# Nixie_MCU_PWR.net
KiCad netlist of a schematic drawn in Altium Designer
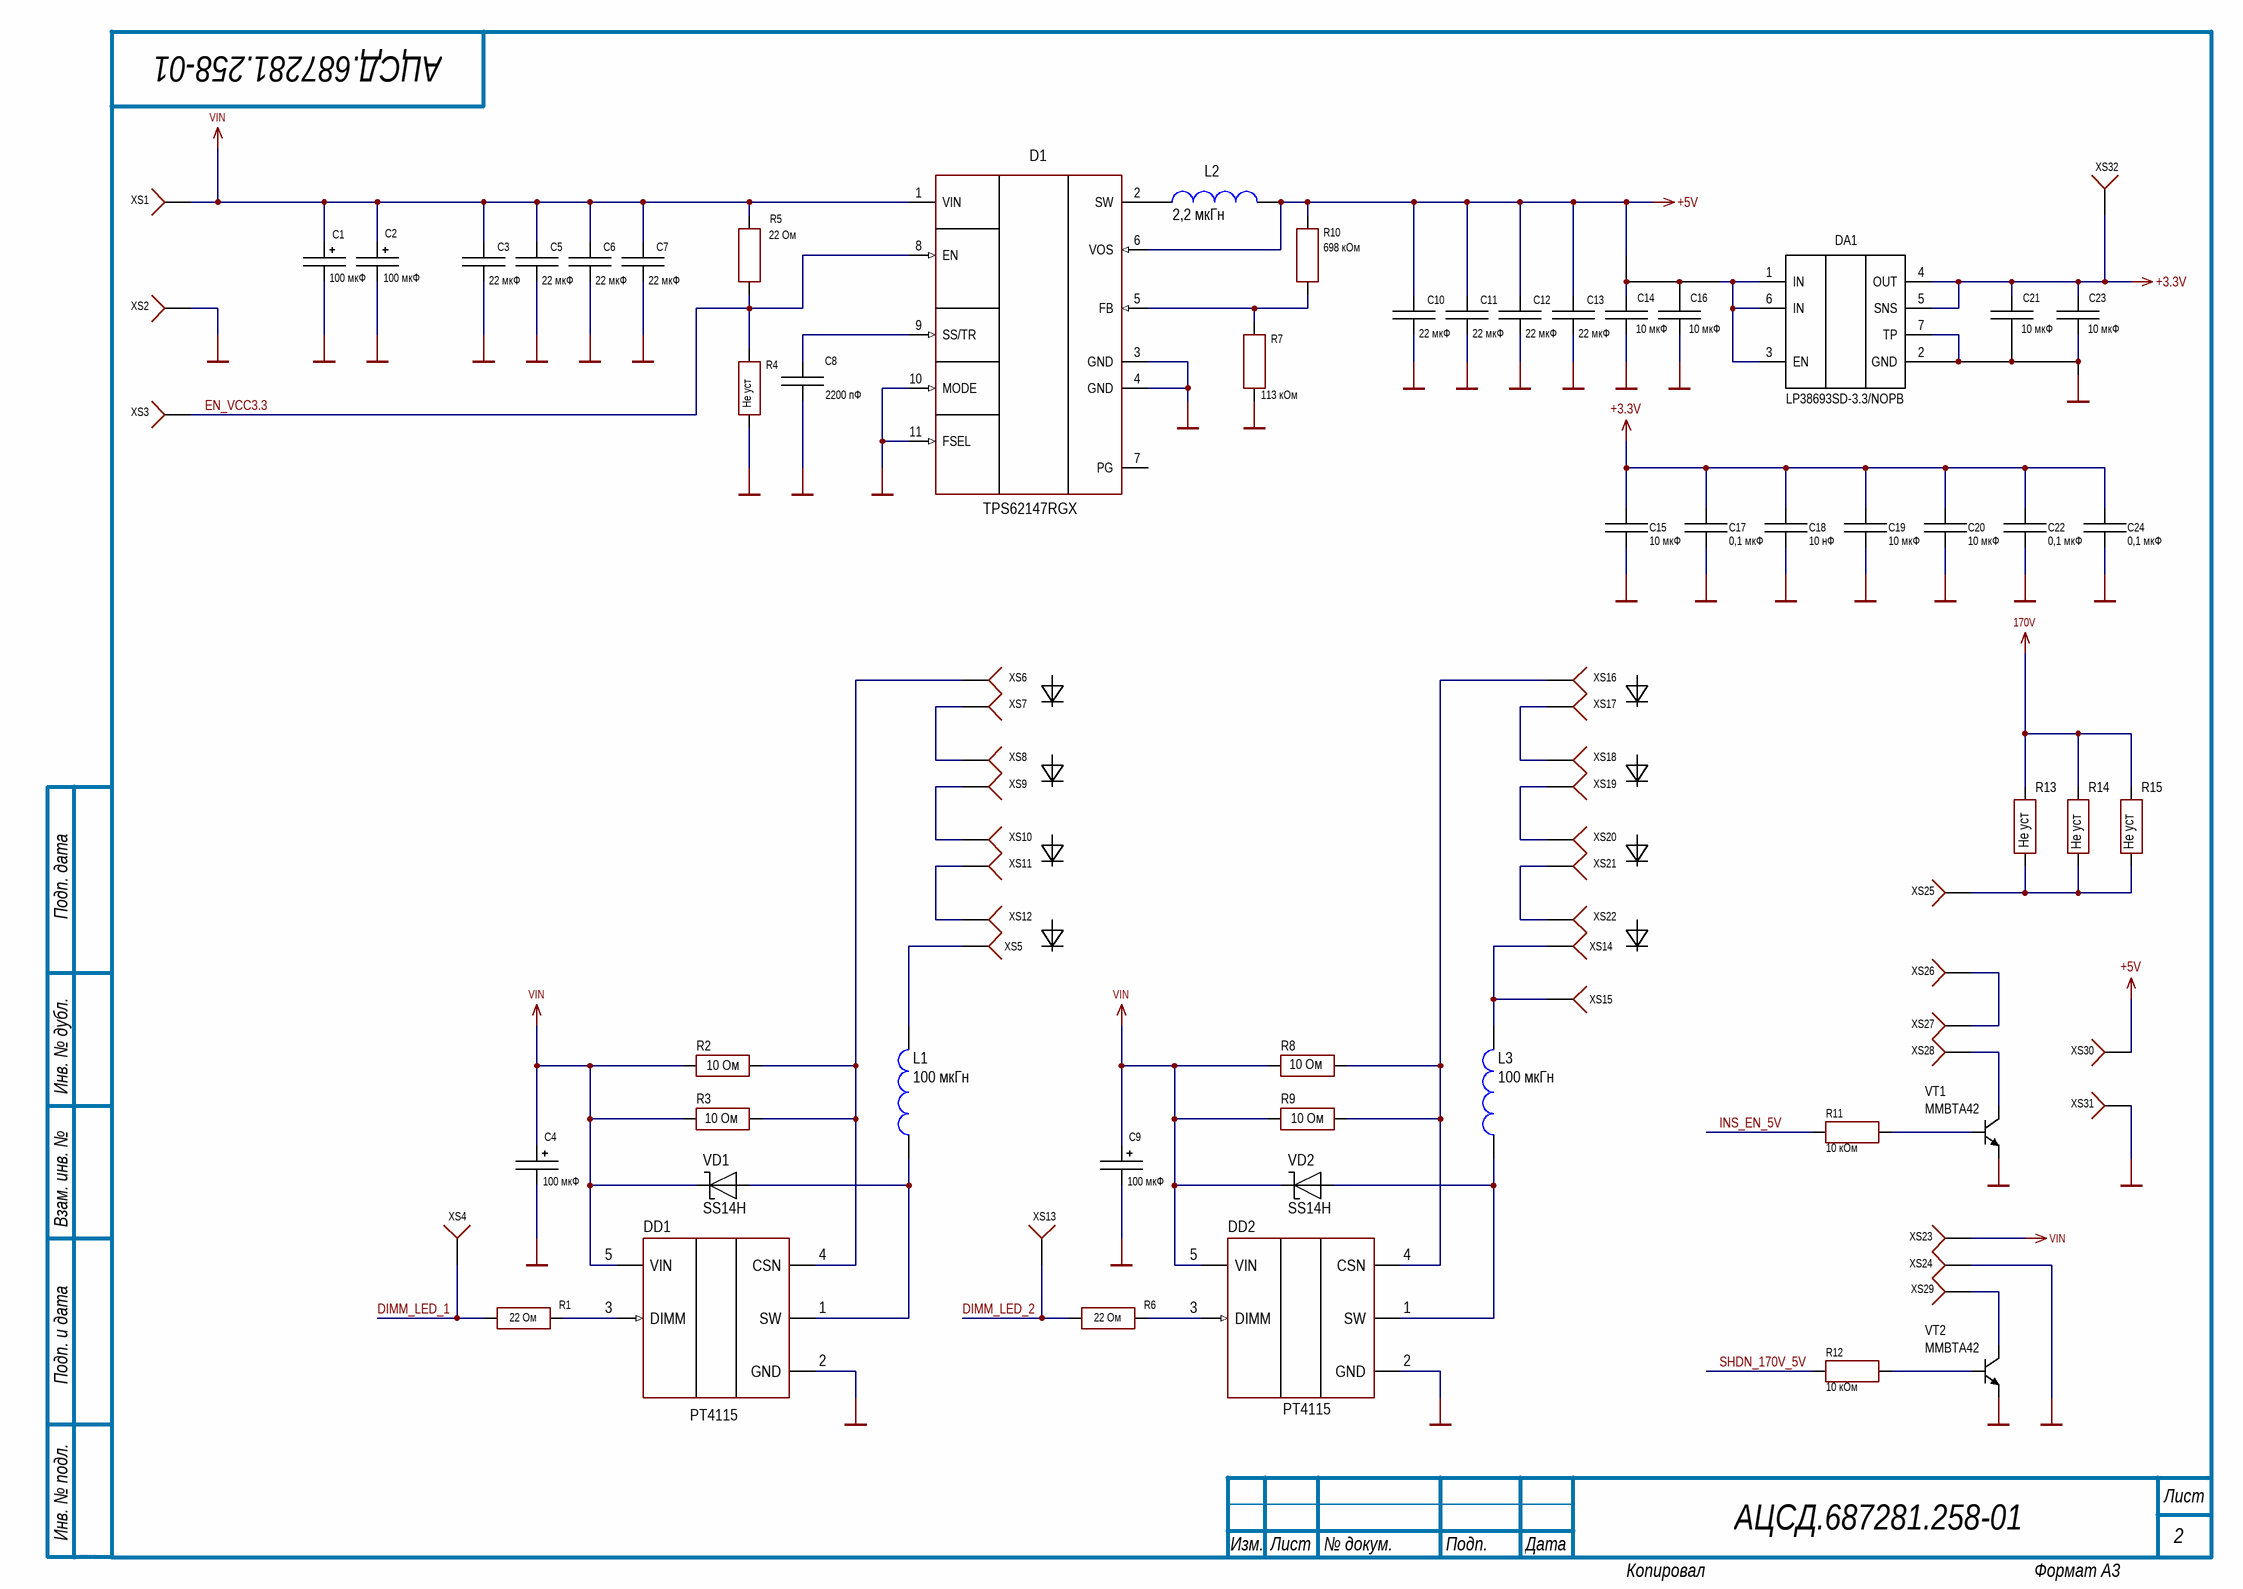
[diagram p0: Nixie_MCU_PWR.SchDoc]

(export (version "E")
  (design (tool "Eeschema 10.0.6"))
  (components
    (comp (ref "C1")
      (value "100 мкФ")
      (footprint "CAP: D5H5.8")
      (fields
        (field (name "MANUFACTURER") "Panasonic")
        (field (name "PARTNUMBER") "EEE-FT1C101AR")
        (field (name "VALUEMANUFACTURERPARTNUMBER") "Aluminium capacitor, 100 мкФ, , ±20%, , 5×5×5.3, -55...+105°C")
      )
      (libsource (lib "Capacitor") (part "Aluminium"))
    )
    (comp (ref "C2")
      (value "100 мкФ")
      (footprint "CAP: D5H5.8")
      (fields
        (field (name "MANUFACTURER") "Panasonic")
        (field (name "PARTNUMBER") "EEE-FT1C101AR")
        (field (name "VALUEMANUFACTURERPARTNUMBER") "Aluminium capacitor, 100 мкФ, , ±20%, , 5×5×5.3, -55...+105°C")
      )
      (libsource (lib "Capacitor") (part "Aluminium"))
    )
    (comp (ref "C3")
      (value "22 мкФ")
      (footprint "CAP: 0805R")
      (fields (field (name "TOLERANCE") "±20%"))
      (libsource (lib "") (part "Ceramic_0603_1"))
    )
    (comp (ref "C4")
      (value "100 мкФ")
      (footprint "CAP: D5H5.8")
      (fields
        (field (name "MANUFACTURER") "Panasonic")
        (field (name "PARTNUMBER") "EEE-FT1C101AR")
        (field (name "VALUEMANUFACTURERPARTNUMBER") "Aluminium capacitor, 100 мкФ, , ±20%, , 5×5×5.3, -55...+105°C")
      )
      (libsource (lib "Capacitor") (part "Aluminium"))
    )
    (comp (ref "C5")
      (value "22 мкФ")
      (footprint "CAP: 0805R")
      (fields (field (name "TOLERANCE") "±20%"))
      (libsource (lib "") (part "Ceramic_0603_1"))
    )
    (comp (ref "C6")
      (value "22 мкФ")
      (footprint "CAP: 0805R")
      (fields (field (name "TOLERANCE") "±20%"))
      (libsource (lib "") (part "Ceramic_0603_1"))
    )
    (comp (ref "C7")
      (value "22 мкФ")
      (footprint "CAP: 0805R")
      (fields (field (name "TOLERANCE") "±20%"))
      (libsource (lib "") (part "Ceramic_0603_1"))
    )
    (comp (ref "C8")
      (value "2200 пФ")
      (footprint "CAP: 0402R")
      (fields
        (field (name "MANUFACTURER") "Murata")
        (field (name "VALUEMANUFACTURERPARTNUMBER") "Ceramic capacitor, 2200 пФ, X7R, ± 10 %, , 0402, -55...+125°C")
        (field (name "TOLERANCE") "± 10 %")
      )
      (libsource (lib "Capacitor") (part "Ceramic_0402"))
    )
    (comp (ref "C9")
      (value "100 мкФ")
      (footprint "CAP: D5H5.8")
      (fields
        (field (name "MANUFACTURER") "Panasonic")
        (field (name "PARTNUMBER") "EEE-FT1C101AR")
        (field (name "VALUEMANUFACTURERPARTNUMBER") "Aluminium capacitor, 100 мкФ, , ±20%, , 5×5×5.3, -55...+105°C")
      )
      (libsource (lib "Capacitor") (part "Aluminium"))
    )
    (comp (ref "C10")
      (value "22 мкФ")
      (footprint "CAP: 0805R")
      (fields (field (name "TOLERANCE") "±20%"))
      (libsource (lib "") (part "Ceramic_0603_1"))
    )
    (comp (ref "C11")
      (value "22 мкФ")
      (footprint "CAP: 0805R")
      (fields (field (name "TOLERANCE") "±20%"))
      (libsource (lib "") (part "Ceramic_0603_1"))
    )
    (comp (ref "C12")
      (value "22 мкФ")
      (footprint "CAP: 0805R")
      (fields (field (name "TOLERANCE") "±20%"))
      (libsource (lib "") (part "Ceramic_0603_1"))
    )
    (comp (ref "C13")
      (value "22 мкФ")
      (footprint "CAP: 0805R")
      (fields (field (name "TOLERANCE") "±20%"))
      (libsource (lib "") (part "Ceramic_0603_1"))
    )
    (comp (ref "C14")
      (value "10 мкФ")
      (footprint "CAP: 0603R")
      (fields
        (field (name "MANUFACTURER") "Yageo")
        (field (name "VALUEMANUFACTURERPARTNUMBER") "Ceramic capacitor, 10 мкФ, X7R, ±10%, 16V, 0603, -55...+125°C")
        (field (name "TOLERANCE") "±10%")
      )
      (libsource (lib "Capacitor") (part "Ceramic_0603"))
    )
    (comp (ref "C15")
      (value "10 мкФ")
      (footprint "CAP: 0603R")
      (fields
        (field (name "MANUFACTURER") "Yageo")
        (field (name "VALUEMANUFACTURERPARTNUMBER") "Ceramic capacitor, 10 мкФ, X7R, ±10%, 16V, 0603, -55...+125°C")
        (field (name "TOLERANCE") "±10%")
      )
      (libsource (lib "Capacitor") (part "Ceramic_0603"))
    )
    (comp (ref "C16")
      (value "10 мкФ")
      (footprint "CAP: 0603R")
      (fields
        (field (name "MANUFACTURER") "Yageo")
        (field (name "VALUEMANUFACTURERPARTNUMBER") "Ceramic capacitor, 10 мкФ, X7R, ±10%, 16V, 0603, -55...+125°C")
        (field (name "TOLERANCE") "±10%")
      )
      (libsource (lib "Capacitor") (part "Ceramic_0603"))
    )
    (comp (ref "C17")
      (value "0,1 мкФ")
      (footprint "CAP: 0402R")
      (fields
        (field (name "MANUFACTURER") "Murata")
        (field (name "PARTNUMBER") "GCM155R71H104KE02#")
        (field (name "VALUEMANUFACTURERPARTNUMBER") "Ceramic capacitor, 0,1 мкФ, X7R, ± 10 %, , 0402, -55...+125°C")
      )
      (libsource (lib "Capacitor") (part "Ceramic_0402"))
    )
    (comp (ref "C18")
      (value "10 нФ")
      (footprint "CAP: 0402R")
      (fields
        (field (name "MANUFACTURER") "Murata")
        (field (name "PARTNUMBER") "GCM155R71H104KE02#")
        (field (name "VALUEMANUFACTURERPARTNUMBER") "Ceramic capacitor, 10 нФ, X7R, ± 10 %, , 0402, -55...+125°C")
      )
      (libsource (lib "Capacitor") (part "Ceramic_0402"))
    )
    (comp (ref "C19")
      (value "10 мкФ")
      (footprint "CAP: 0603R")
      (fields
        (field (name "MANUFACTURER") "Yageo")
        (field (name "VALUEMANUFACTURERPARTNUMBER") "Ceramic capacitor, 10 мкФ, X7R, ±10%, 16V, 0603, -55...+125°C")
        (field (name "TOLERANCE") "±10%")
      )
      (libsource (lib "Capacitor") (part "Ceramic_0603"))
    )
    (comp (ref "C20")
      (value "10 мкФ")
      (footprint "CAP: 0603R")
      (fields
        (field (name "MANUFACTURER") "Yageo")
        (field (name "VALUEMANUFACTURERPARTNUMBER") "Ceramic capacitor, 10 мкФ, X7R, ±10%, 16V, 0603, -55...+125°C")
        (field (name "TOLERANCE") "±10%")
      )
      (libsource (lib "Capacitor") (part "Ceramic_0603"))
    )
    (comp (ref "C21")
      (value "10 мкФ")
      (footprint "CAP: 0603R")
      (fields
        (field (name "MANUFACTURER") "Yageo")
        (field (name "VALUEMANUFACTURERPARTNUMBER") "Ceramic capacitor, 10 мкФ, X7R, ±10%, 16V, 0603, -55...+125°C")
        (field (name "TOLERANCE") "±10%")
      )
      (libsource (lib "Capacitor") (part "Ceramic_0603"))
    )
    (comp (ref "C22")
      (value "0,1 мкФ")
      (footprint "CAP: 0402R")
      (fields
        (field (name "MANUFACTURER") "Murata")
        (field (name "PARTNUMBER") "GCM155R71H104KE02#")
        (field (name "VALUEMANUFACTURERPARTNUMBER") "Ceramic capacitor, 0,1 мкФ, X7R, ± 10 %, , 0402, -55...+125°C")
      )
      (libsource (lib "Capacitor") (part "Ceramic_0402"))
    )
    (comp (ref "C23")
      (value "10 мкФ")
      (footprint "CAP: 0603R")
      (fields
        (field (name "MANUFACTURER") "Yageo")
        (field (name "VALUEMANUFACTURERPARTNUMBER") "Ceramic capacitor, 10 мкФ, X7R, ±10%, 16V, 0603, -55...+125°C")
        (field (name "TOLERANCE") "±10%")
      )
      (libsource (lib "Capacitor") (part "Ceramic_0603"))
    )
    (comp (ref "C24")
      (value "0,1 мкФ")
      (footprint "CAP: 0402R")
      (fields
        (field (name "MANUFACTURER") "Murata")
        (field (name "PARTNUMBER") "GCM155R71H104KE02#")
        (field (name "VALUEMANUFACTURERPARTNUMBER") "Ceramic capacitor, 0,1 мкФ, X7R, ± 10 %, , 0402, -55...+125°C")
      )
      (libsource (lib "Capacitor") (part "Ceramic_0402"))
    )
    (comp (ref "D1")
      (value "~")
      (footprint "11-VQFN(RGX)")
      (description "3-V to 17-V 2-A Step-Down Converters")
      (fields (field (name "MANUFACTURER") "Texas Instruments") (field (name "PARTNUMBER") "TPS62147RGX"))
      (libsource (lib "IC. Power supply") (part "TPS62147RGX"))
    )
    (comp (ref "DA1")
      (value "LP38693SD-3.3/NOPB")
      (footprint "StandardCase:6-WSON")
      (description "LINEAR 3.3V 500MA 6WSON")
      (fields
        (field (name "MANUFACTURER") "Texas Instruments")
        (field (name "VALUEMANUFACTURERPARTNUMBER") "LDO, (2.7 V to 10 V), , output 3.3V, 500 mA, -40…+125, WSON (6)")
      )
      (libsource (lib "IC. Power supply") (part "LP38693SD-3.3/NOPB"))
    )
    (comp (ref "DD1")
      (value "~")
      (footprint "5-SOT-89")
      (description "LED current driver")
      (fields
        (field (name "VALUEMANUFACTURERPARTNUMBER") "LED current driver, 6 V to 30 v, , , 1.2A, -40…+125, SOT89-5")
        (field (name "PARTNUMBER") "PT4115")
      )
      (libsource (lib "IC. Power supply") (part "PT4115"))
    )
    (comp (ref "DD2")
      (value "~")
      (footprint "5-SOT-89")
      (description "LED current driver")
      (fields
        (field (name "VALUEMANUFACTURERPARTNUMBER") "LED current driver, 6 V to 30 v, , , 1.2A, -40…+125, SOT89-5")
        (field (name "PARTNUMBER") "PT4115")
      )
      (libsource (lib "IC. Power supply") (part "PT4115"))
    )
    (comp (ref "L1")
      (value "100 мкГн")
      (footprint "IND: VLS5045EX")
      (description "Power Inductor, 5.0x5.0x4.5mm, -40°C to +105°C")
      (fields
        (field (name "PARTNUMBER") "VLS5045EX-101M")
        (field (name "VALUEMANUFACTURERPARTNUMBER") "Fixed inductor, 100 мкГн, , , , -40...+125°C")
      )
      (libsource (lib "Inductor") (part "VLS5045EX"))
    )
    (comp (ref "L2")
      (value "2,2 мкГн")
      (footprint "IND: VLS5045EX")
      (description "Power Inductor, 5.0x5.0x4.5mm, -40°C to +105°C")
      (fields
        (field (name "PARTNUMBER") "VLS5045EX-2R2N")
        (field (name "VALUEMANUFACTURERPARTNUMBER") "Fixed inductor, 2,2 мкГн, , , , -40...+125°C")
      )
      (libsource (lib "Inductor") (part "VLS5045EX"))
    )
    (comp (ref "L3")
      (value "100 мкГн")
      (footprint "IND: VLS5045EX")
      (description "Power Inductor, 5.0x5.0x4.5mm, -40°C to +105°C")
      (fields
        (field (name "PARTNUMBER") "VLS5045EX-101M")
        (field (name "VALUEMANUFACTURERPARTNUMBER") "Fixed inductor, 100 мкГн, , , , -40...+125°C")
      )
      (libsource (lib "Inductor") (part "VLS5045EX"))
    )
    (comp (ref "R1")
      (value "22 Ом")
      (footprint "RES: 0402_ASK")
      (fields (field (name "POWER") "0.063 Вт") (field (name "TOLERANCE") "±1%"))
      (libsource (lib "") (part "Resistor_0402_2"))
    )
    (comp (ref "R2")
      (value "10 Ом")
      (footprint "RES: 0603_ASK")
      (fields
        (field (name "MANUFACTURER") "Yageo")
        (field (name "PARTNUMBER") "RC0603JR-07100RL")
        (field (name "VALUEMANUFACTURERPARTNUMBER") "Resistor film, 10 Ом, ±1%, 0603, 0.1W, -55...+125°C")
      )
      (libsource (lib "Resistor") (part "Resistor_0603"))
    )
    (comp (ref "R3")
      (value "10 Ом")
      (footprint "RES: 0603_ASK")
      (fields
        (field (name "MANUFACTURER") "Yageo")
        (field (name "PARTNUMBER") "RC0603JR-07100RL")
        (field (name "VALUEMANUFACTURERPARTNUMBER") "Resistor film, 10 Ом, ±1%, 0603, 0.1W, -55...+125°C")
      )
      (libsource (lib "Resistor") (part "Resistor_0603"))
    )
    (comp (ref "R4")
      (value "Не уст")
      (footprint "RES: 0402_ASK")
      (fields (field (name "POWER") "0.063 Вт") (field (name "TOLERANCE") "±1%"))
      (libsource (lib "Resistor") (part "Resistor_0402"))
    )
    (comp (ref "R5")
      (value "22 Ом")
      (footprint "RES: 0402_ASK")
      (fields (field (name "POWER") "0.063 Вт") (field (name "TOLERANCE") "±1%"))
      (libsource (lib "Resistor") (part "Resistor_0402"))
    )
    (comp (ref "R6")
      (value "22 Ом")
      (footprint "RES: 0402_ASK")
      (fields (field (name "POWER") "0.063 Вт") (field (name "TOLERANCE") "±1%"))
      (libsource (lib "") (part "Resistor_0402_2"))
    )
    (comp (ref "R7")
      (value "113 кОм")
      (footprint "RES: 0402_ASK")
      (fields (field (name "POWER") "0.063 Вт") (field (name "TOLERANCE") "±1%"))
      (libsource (lib "Resistor") (part "Resistor_0402"))
    )
    (comp (ref "R8")
      (value "10 Ом")
      (footprint "RES: 0603_ASK")
      (fields
        (field (name "MANUFACTURER") "Yageo")
        (field (name "PARTNUMBER") "RC0603JR-07100RL")
        (field (name "VALUEMANUFACTURERPARTNUMBER") "Resistor film, 10 Ом, ±1%, 0603, 0.1W, -55...+125°C")
      )
      (libsource (lib "Resistor") (part "Resistor_0603"))
    )
    (comp (ref "R9")
      (value "10 Ом")
      (footprint "RES: 0603_ASK")
      (fields
        (field (name "MANUFACTURER") "Yageo")
        (field (name "PARTNUMBER") "RC0603JR-07100RL")
        (field (name "VALUEMANUFACTURERPARTNUMBER") "Resistor film, 10 Ом, ±1%, 0603, 0.1W, -55...+125°C")
      )
      (libsource (lib "Resistor") (part "Resistor_0603"))
    )
    (comp (ref "R10")
      (value "698 кОм")
      (footprint "RES: 0402_ASK")
      (fields (field (name "POWER") "0.063 Вт") (field (name "TOLERANCE") "±1%"))
      (libsource (lib "Resistor") (part "Resistor_0402"))
    )
    (comp (ref "R11")
      (value "10 кОм")
      (footprint "RES: 0402_ASK")
      (fields (field (name "POWER") "0.063 Вт") (field (name "TOLERANCE") "±1%"))
      (libsource (lib "") (part "Resistor_0402_1"))
    )
    (comp (ref "R12")
      (value "10 кОм")
      (footprint "RES: 0402_ASK")
      (fields (field (name "POWER") "0.063 Вт") (field (name "TOLERANCE") "±1%"))
      (libsource (lib "") (part "Resistor_0402_1"))
    )
    (comp (ref "R13")
      (value "Не уст")
      (footprint "RES: 0603_ASK")
      (fields
        (field (name "MANUFACTURER") "Yageo")
        (field (name "PARTNUMBER") "RC0603JR-07100RL")
        (field (name "VALUEMANUFACTURERPARTNUMBER") "Resistor film, Не уст, ±1%, 0603, 0.1W, -55...+125°C")
      )
      (libsource (lib "") (part "Resistor_0603_1"))
    )
    (comp (ref "R14")
      (value "Не уст")
      (footprint "RES: 0603_ASK")
      (fields
        (field (name "MANUFACTURER") "Yageo")
        (field (name "PARTNUMBER") "RC0603JR-07100RL")
        (field (name "VALUEMANUFACTURERPARTNUMBER") "Resistor film, Не уст, ±1%, 0603, 0.1W, -55...+125°C")
      )
      (libsource (lib "") (part "Resistor_0603_1"))
    )
    (comp (ref "R15")
      (value "Не уст")
      (footprint "RES: 0603_ASK")
      (fields
        (field (name "MANUFACTURER") "Yageo")
        (field (name "PARTNUMBER") "RC0603JR-07100RL")
        (field (name "VALUEMANUFACTURERPARTNUMBER") "Resistor film, Не уст, ±1%, 0603, 0.1W, -55...+125°C")
      )
      (libsource (lib "") (part "Resistor_0603_1"))
    )
    (comp (ref "VD1")
      (value "~")
      (footprint "StandardCase:DIODE: SMA")
      (fields
        (field (name "MANUFACTURER") "Diodes Incorporated")
        (field (name "VALUEMANUFACTURERPARTNUMBER") "Schottky diode, 80V, 500mA, 1V, 15pF, SOD-123, -55...+150°C")
        (field (name "VOLTAGE") "80V")
        (field (name "PARTNUMBER") "SS14H")
      )
      (libsource (lib "Diode") (part "Schottky_single"))
    )
    (comp (ref "VD2")
      (value "~")
      (footprint "StandardCase:DIODE: SMA")
      (fields
        (field (name "MANUFACTURER") "Diodes Incorporated")
        (field (name "VALUEMANUFACTURERPARTNUMBER") "Schottky diode, 80V, 500mA, 1V, 15pF, SOD-123, -55...+150°C")
        (field (name "VOLTAGE") "80V")
        (field (name "PARTNUMBER") "SS14H")
      )
      (libsource (lib "Diode") (part "Schottky_single"))
    )
    (comp (ref "VT1")
      (value "~")
      (footprint "StandardCase:SOT23")
      (fields
        (field (name "MANUFACTURER") "ON Semiconductor")
        (field (name "VALUEMANUFACTURERPARTNUMBER") "NPN transistor, 45V, 100mA, 100MHz, 300mW, 0.6V, 420, SOT-23, -55...+125°C")
        (field (name "PARTNUMBER") "MMBTA42")
      )
      (libsource (lib "Transistor") (part "BJT_NPN_132"))
    )
    (comp (ref "VT2")
      (value "~")
      (footprint "StandardCase:SOT23")
      (fields
        (field (name "MANUFACTURER") "ON Semiconductor")
        (field (name "VALUEMANUFACTURERPARTNUMBER") "NPN transistor, 45V, 100mA, 100MHz, 300mW, 0.6V, 420, SOT-23, -55...+125°C")
        (field (name "PARTNUMBER") "MMBTA42")
      )
      (libsource (lib "Transistor") (part "BJT_NPN_132"))
    )
    (comp (ref "XS1") (value "~") (footprint "CON: PLD-1") (libsource (lib "Connector") (part "Контр.точка")))
    (comp (ref "XS2") (value "~") (footprint "CON: PLD-1") (libsource (lib "Connector") (part "Контр.точка")))
    (comp (ref "XS3") (value "~") (footprint "CON: PLD-1") (libsource (lib "Connector") (part "Контр.точка")))
    (comp (ref "XS4") (value "~") (footprint "CON: PLD-1") (libsource (lib "Connector") (part "Контр.точка")))
    (comp (ref "XS5") (value "~") (footprint "CON: PLD-1") (libsource (lib "Connector") (part "Контр.точка")))
    (comp (ref "XS6") (value "~") (footprint "CON: PLD-1") (libsource (lib "Connector") (part "Контр.точка")))
    (comp (ref "XS7") (value "~") (footprint "CON: PLD-1") (libsource (lib "Connector") (part "Контр.точка")))
    (comp (ref "XS8") (value "~") (footprint "CON: PLD-1") (libsource (lib "Connector") (part "Контр.точка")))
    (comp (ref "XS9") (value "~") (footprint "CON: PLD-1") (libsource (lib "Connector") (part "Контр.точка")))
    (comp (ref "XS10")
      (value "~")
      (footprint "CON: PLD-1")
      (libsource (lib "Connector") (part "Контр.точка"))
    )
    (comp (ref "XS11")
      (value "~")
      (footprint "CON: PLD-1")
      (libsource (lib "Connector") (part "Контр.точка"))
    )
    (comp (ref "XS12")
      (value "~")
      (footprint "CON: PLD-1")
      (libsource (lib "Connector") (part "Контр.точка"))
    )
    (comp (ref "XS13")
      (value "~")
      (footprint "CON: PLD-1")
      (libsource (lib "Connector") (part "Контр.точка"))
    )
    (comp (ref "XS14")
      (value "~")
      (footprint "CON: PLD-1")
      (libsource (lib "Connector") (part "Контр.точка"))
    )
    (comp (ref "XS15")
      (value "~")
      (footprint "CON: PLD-1")
      (libsource (lib "Connector") (part "Контр.точка"))
    )
    (comp (ref "XS16")
      (value "~")
      (footprint "CON: PLD-1")
      (libsource (lib "Connector") (part "Контр.точка"))
    )
    (comp (ref "XS17")
      (value "~")
      (footprint "CON: PLD-1")
      (libsource (lib "Connector") (part "Контр.точка"))
    )
    (comp (ref "XS18")
      (value "~")
      (footprint "CON: PLD-1")
      (libsource (lib "Connector") (part "Контр.точка"))
    )
    (comp (ref "XS19")
      (value "~")
      (footprint "CON: PLD-1")
      (libsource (lib "Connector") (part "Контр.точка"))
    )
    (comp (ref "XS20")
      (value "~")
      (footprint "CON: PLD-1")
      (libsource (lib "Connector") (part "Контр.точка"))
    )
    (comp (ref "XS21")
      (value "~")
      (footprint "CON: PLD-1")
      (libsource (lib "Connector") (part "Контр.точка"))
    )
    (comp (ref "XS22")
      (value "~")
      (footprint "CON: PLD-1")
      (libsource (lib "Connector") (part "Контр.точка"))
    )
    (comp (ref "XS23")
      (value "~")
      (footprint "CON: PLD-1")
      (libsource (lib "Connector") (part "Контр.точка"))
    )
    (comp (ref "XS24")
      (value "~")
      (footprint "CON: PLD-1")
      (libsource (lib "Connector") (part "Контр.точка"))
    )
    (comp (ref "XS25")
      (value "~")
      (footprint "CON: PLD-1")
      (libsource (lib "Connector") (part "Контр.точка"))
    )
    (comp (ref "XS26")
      (value "~")
      (footprint "CON: PLD-1")
      (libsource (lib "Connector") (part "Контр.точка"))
    )
    (comp (ref "XS27")
      (value "~")
      (footprint "CON: PLD-1")
      (libsource (lib "Connector") (part "Контр.точка"))
    )
    (comp (ref "XS28")
      (value "~")
      (footprint "CON: PLD-1")
      (libsource (lib "Connector") (part "Контр.точка"))
    )
    (comp (ref "XS29")
      (value "~")
      (footprint "CON: PLD-1")
      (libsource (lib "Connector") (part "Контр.точка"))
    )
    (comp (ref "XS30")
      (value "~")
      (footprint "CON: PLD-1")
      (libsource (lib "Connector") (part "Контр.точка"))
    )
    (comp (ref "XS31")
      (value "~")
      (footprint "CON: PLD-1")
      (libsource (lib "Connector") (part "Контр.точка"))
    )
    (comp (ref "XS32")
      (value "~")
      (footprint "CON: PLD-1")
      (libsource (lib "Connector") (part "Контр.точка"))
    )
  )
  (nets
    (net (code "1") (name "+3.3V") (class "Default")
      (node (ref "C15") (pin "2") (pinfunction "2_2") (pintype "power_in"))
      (node (ref "C17") (pin "2") (pinfunction "2_2") (pintype "passive"))
      (node (ref "C18") (pin "2") (pinfunction "2_2") (pintype "passive"))
      (node (ref "C19") (pin "2") (pinfunction "2_2") (pintype "power_in"))
      (node (ref "C20") (pin "2") (pinfunction "2_2") (pintype "power_in"))
      (node (ref "C21") (pin "2") (pinfunction "2_2") (pintype "power_in"))
      (node (ref "C22") (pin "2") (pinfunction "2_2") (pintype "passive"))
      (node (ref "C23") (pin "2") (pinfunction "2_2") (pintype "power_in"))
      (node (ref "C24") (pin "2") (pinfunction "2_2") (pintype "passive"))
      (node (ref "DA1") (pin "4") (pinfunction "OUT_4") (pintype "passive"))
      (node (ref "DA1") (pin "5") (pinfunction "SNS_5") (pintype "passive"))
      (node (ref "XS32") (pin "1") (pinfunction "1_1") (pintype "passive"))
    )
    (net (code "2") (name "+5V") (class "Default")
      (node (ref "C10") (pin "2") (pinfunction "2_2") (pintype "passive"))
      (node (ref "C11") (pin "2") (pinfunction "2_2") (pintype "passive"))
      (node (ref "C12") (pin "2") (pinfunction "2_2") (pintype "passive"))
      (node (ref "C13") (pin "2") (pinfunction "2_2") (pintype "passive"))
      (node (ref "C14") (pin "2") (pinfunction "2_2") (pintype "power_in"))
      (node (ref "C16") (pin "2") (pinfunction "2_2") (pintype "power_in"))
      (node (ref "D1") (pin "6") (pinfunction "VOS_6") (pintype "input"))
      (node (ref "DA1") (pin "1") (pinfunction "IN_1") (pintype "passive"))
      (node (ref "DA1") (pin "3") (pinfunction "EN_3") (pintype "passive"))
      (node (ref "DA1") (pin "6") (pinfunction "IN_6") (pintype "passive"))
      (node (ref "L2") (pin "2") (pinfunction "2_2") (pintype "passive"))
      (node (ref "R10") (pin "1") (pinfunction "1_1") (pintype "passive"))
      (node (ref "XS30") (pin "1") (pinfunction "1_1") (pintype "passive"))
    )
    (net (code "3") (name "/DIMM_LED_1") (class "Default")
      (node (ref "R1") (pin "1") (pinfunction "1_1") (pintype "passive"))
      (node (ref "XS4") (pin "1") (pinfunction "1_1") (pintype "passive"))
    )
    (net (code "4") (name "/DIMM_LED_2") (class "Default")
      (node (ref "R6") (pin "1") (pinfunction "1_1") (pintype "passive"))
      (node (ref "XS13") (pin "1") (pinfunction "1_1") (pintype "passive"))
    )
    (net (code "5") (name "/EN_VCC3.3") (class "Default")
      (node (ref "D1") (pin "8") (pinfunction "EN_8") (pintype "input"))
      (node (ref "R4") (pin "1") (pinfunction "1_1") (pintype "passive"))
      (node (ref "R5") (pin "2") (pinfunction "2_2") (pintype "passive"))
      (node (ref "XS3") (pin "1") (pinfunction "1_1") (pintype "passive"))
    )
    (net (code "6") (name "/INS_EN_5V") (class "Default")
      (node (ref "R11") (pin "2") (pinfunction "2_2") (pintype "passive"))
    )
    (net (code "7") (name "/SHDN_170V_5V") (class "Default")
      (node (ref "R12") (pin "2") (pinfunction "2_2") (pintype "passive"))
    )
    (net (code "8") (name "170V") (class "Default")
      (node (ref "R13") (pin "2") (pinfunction "2_2") (pintype "passive"))
      (node (ref "R14") (pin "2") (pinfunction "2_2") (pintype "passive"))
      (node (ref "R15") (pin "2") (pinfunction "2_2") (pintype "passive"))
    )
    (net (code "9") (name "GND") (class "Default")
      (node (ref "C1") (pin "2") (pinfunction "2_2") (pintype "power_in"))
      (node (ref "C10") (pin "1") (pinfunction "1_1") (pintype "power_in"))
      (node (ref "C11") (pin "1") (pinfunction "1_1") (pintype "power_in"))
      (node (ref "C12") (pin "1") (pinfunction "1_1") (pintype "power_in"))
      (node (ref "C13") (pin "1") (pinfunction "1_1") (pintype "power_in"))
      (node (ref "C14") (pin "1") (pinfunction "1_1") (pintype "power_in"))
      (node (ref "C15") (pin "1") (pinfunction "1_1") (pintype "power_in"))
      (node (ref "C16") (pin "1") (pinfunction "1_1") (pintype "power_in"))
      (node (ref "C17") (pin "1") (pinfunction "1_1") (pintype "power_in"))
      (node (ref "C18") (pin "1") (pinfunction "1_1") (pintype "power_in"))
      (node (ref "C19") (pin "1") (pinfunction "1_1") (pintype "power_in"))
      (node (ref "C2") (pin "2") (pinfunction "2_2") (pintype "power_in"))
      (node (ref "C20") (pin "1") (pinfunction "1_1") (pintype "power_in"))
      (node (ref "C21") (pin "1") (pinfunction "1_1") (pintype "power_in"))
      (node (ref "C22") (pin "1") (pinfunction "1_1") (pintype "power_in"))
      (node (ref "C23") (pin "1") (pinfunction "1_1") (pintype "power_in"))
      (node (ref "C24") (pin "1") (pinfunction "1_1") (pintype "power_in"))
      (node (ref "C3") (pin "1") (pinfunction "1_1") (pintype "power_in"))
      (node (ref "C4") (pin "2") (pinfunction "2_2") (pintype "power_in"))
      (node (ref "C5") (pin "1") (pinfunction "1_1") (pintype "power_in"))
      (node (ref "C6") (pin "1") (pinfunction "1_1") (pintype "power_in"))
      (node (ref "C7") (pin "1") (pinfunction "1_1") (pintype "power_in"))
      (node (ref "C8") (pin "1") (pinfunction "1_1") (pintype "power_in"))
      (node (ref "C9") (pin "2") (pinfunction "2_2") (pintype "power_in"))
      (node (ref "D1") (pin "10") (pinfunction "MODE_10") (pintype "input"))
      (node (ref "D1") (pin "11") (pinfunction "FSEL_11") (pintype "input"))
      (node (ref "D1") (pin "3") (pinfunction "GND_3") (pintype "passive"))
      (node (ref "D1") (pin "4") (pinfunction "GND_4") (pintype "passive"))
      (node (ref "DA1") (pin "2") (pinfunction "GND_2") (pintype "power_in"))
      (node (ref "DA1") (pin "7") (pinfunction "TP_7") (pintype "passive"))
      (node (ref "DD1") (pin "2") (pinfunction "GND_2") (pintype "passive"))
      (node (ref "DD2") (pin "2") (pinfunction "GND_2") (pintype "passive"))
      (node (ref "R4") (pin "2") (pinfunction "2_2") (pintype "passive"))
      (node (ref "R7") (pin "2") (pinfunction "2_2") (pintype "passive"))
      (node (ref "VT1") (pin "2") (pinfunction "E_2") (pintype "passive"))
      (node (ref "VT2") (pin "2") (pinfunction "E_2") (pintype "passive"))
      (node (ref "XS2") (pin "1") (pinfunction "1_1") (pintype "passive"))
      (node (ref "XS24") (pin "1") (pinfunction "1_1") (pintype "passive"))
      (node (ref "XS31") (pin "1") (pinfunction "1_1") (pintype "passive"))
    )
    (net (code "10") (name "Net-(D1-FB)") (class "Default")
      (node (ref "D1") (pin "5") (pinfunction "FB_5") (pintype "input"))
      (node (ref "R10") (pin "2") (pinfunction "2_2") (pintype "passive"))
      (node (ref "R7") (pin "1") (pinfunction "1_1") (pintype "passive"))
    )
    (net (code "11") (name "Net-(D1-SS{slash}TR)") (class "Default")
      (node (ref "C8") (pin "2") (pinfunction "2_2") (pintype "passive"))
      (node (ref "D1") (pin "9") (pinfunction "SS/TR_9") (pintype "input"))
    )
    (net (code "12") (name "Net-(D1-SW)") (class "Default")
      (node (ref "D1") (pin "2") (pinfunction "SW_2") (pintype "passive"))
      (node (ref "L2") (pin "1") (pinfunction "1_1") (pintype "passive"))
    )
    (net (code "13") (name "Net-(DD1-CSN)") (class "Default")
      (node (ref "DD1") (pin "4") (pinfunction "CSN_4") (pintype "passive"))
      (node (ref "R2") (pin "1") (pinfunction "1_1") (pintype "passive"))
      (node (ref "R3") (pin "1") (pinfunction "1_1") (pintype "passive"))
      (node (ref "XS6") (pin "1") (pinfunction "1_1") (pintype "passive"))
    )
    (net (code "14") (name "Net-(DD1-DIMM)") (class "Default")
      (node (ref "DD1") (pin "3") (pinfunction "DIMM_3") (pintype "input"))
      (node (ref "R1") (pin "2") (pinfunction "2_2") (pintype "passive"))
    )
    (net (code "15") (name "Net-(DD1-SW)") (class "Default")
      (node (ref "DD1") (pin "1") (pinfunction "SW_1") (pintype "passive"))
      (node (ref "L1") (pin "1") (pinfunction "1_1") (pintype "passive"))
      (node (ref "VD1") (pin "1") (pinfunction "1_1") (pintype "passive"))
    )
    (net (code "16") (name "Net-(DD2-CSN)") (class "Default")
      (node (ref "DD2") (pin "4") (pinfunction "CSN_4") (pintype "passive"))
      (node (ref "R8") (pin "1") (pinfunction "1_1") (pintype "passive"))
      (node (ref "R9") (pin "1") (pinfunction "1_1") (pintype "passive"))
      (node (ref "XS16") (pin "1") (pinfunction "1_1") (pintype "passive"))
    )
    (net (code "17") (name "Net-(DD2-DIMM)") (class "Default")
      (node (ref "DD2") (pin "3") (pinfunction "DIMM_3") (pintype "input"))
      (node (ref "R6") (pin "2") (pinfunction "2_2") (pintype "passive"))
    )
    (net (code "18") (name "Net-(DD2-SW)") (class "Default")
      (node (ref "DD2") (pin "1") (pinfunction "SW_1") (pintype "passive"))
      (node (ref "L3") (pin "1") (pinfunction "1_1") (pintype "passive"))
      (node (ref "VD2") (pin "1") (pinfunction "1_1") (pintype "passive"))
    )
    (net (code "19") (name "Net-(L1-Pad2)") (class "Default")
      (node (ref "L1") (pin "2") (pinfunction "2_2") (pintype "passive"))
      (node (ref "XS5") (pin "1") (pinfunction "1_1") (pintype "passive"))
    )
    (net (code "20") (name "Net-(L3-Pad2)") (class "Default")
      (node (ref "L3") (pin "2") (pinfunction "2_2") (pintype "passive"))
      (node (ref "XS14") (pin "1") (pinfunction "1_1") (pintype "passive"))
      (node (ref "XS15") (pin "1") (pinfunction "1_1") (pintype "passive"))
    )
    (net (code "21") (name "Net-(R13-Pad1)") (class "Default")
      (node (ref "R13") (pin "1") (pinfunction "1_1") (pintype "passive"))
      (node (ref "R14") (pin "1") (pinfunction "1_1") (pintype "passive"))
      (node (ref "R15") (pin "1") (pinfunction "1_1") (pintype "passive"))
      (node (ref "XS25") (pin "1") (pinfunction "1_1") (pintype "passive"))
    )
    (net (code "22") (name "Net-(VT1-B)") (class "Default")
      (node (ref "R11") (pin "1") (pinfunction "1_1") (pintype "passive"))
      (node (ref "VT1") (pin "1") (pinfunction "B_1") (pintype "passive"))
    )
    (net (code "23") (name "Net-(VT1-C)") (class "Default")
      (node (ref "VT1") (pin "3") (pinfunction "C_3") (pintype "passive"))
      (node (ref "XS28") (pin "1") (pinfunction "1_1") (pintype "passive"))
    )
    (net (code "24") (name "Net-(VT2-B)") (class "Default")
      (node (ref "R12") (pin "1") (pinfunction "1_1") (pintype "passive"))
      (node (ref "VT2") (pin "1") (pinfunction "B_1") (pintype "passive"))
    )
    (net (code "25") (name "Net-(VT2-C)") (class "Default")
      (node (ref "VT2") (pin "3") (pinfunction "C_3") (pintype "passive"))
      (node (ref "XS29") (pin "1") (pinfunction "1_1") (pintype "passive"))
    )
    (net (code "26") (name "Net-(XS7-Pad1)") (class "Default")
      (node (ref "XS7") (pin "1") (pinfunction "1_1") (pintype "passive"))
      (node (ref "XS8") (pin "1") (pinfunction "1_1") (pintype "passive"))
    )
    (net (code "27") (name "Net-(XS10-Pad1)") (class "Default")
      (node (ref "XS10") (pin "1") (pinfunction "1_1") (pintype "passive"))
      (node (ref "XS9") (pin "1") (pinfunction "1_1") (pintype "passive"))
    )
    (net (code "28") (name "Net-(XS11-Pad1)") (class "Default")
      (node (ref "XS11") (pin "1") (pinfunction "1_1") (pintype "passive"))
      (node (ref "XS12") (pin "1") (pinfunction "1_1") (pintype "passive"))
    )
    (net (code "29") (name "Net-(XS17-Pad1)") (class "Default")
      (node (ref "XS17") (pin "1") (pinfunction "1_1") (pintype "passive"))
      (node (ref "XS18") (pin "1") (pinfunction "1_1") (pintype "passive"))
    )
    (net (code "30") (name "Net-(XS19-Pad1)") (class "Default")
      (node (ref "XS19") (pin "1") (pinfunction "1_1") (pintype "passive"))
      (node (ref "XS20") (pin "1") (pinfunction "1_1") (pintype "passive"))
    )
    (net (code "31") (name "Net-(XS21-Pad1)") (class "Default")
      (node (ref "XS21") (pin "1") (pinfunction "1_1") (pintype "passive"))
      (node (ref "XS22") (pin "1") (pinfunction "1_1") (pintype "passive"))
    )
    (net (code "32") (name "Net-(XS26-Pad1)") (class "Default")
      (node (ref "XS26") (pin "1") (pinfunction "1_1") (pintype "passive"))
      (node (ref "XS27") (pin "1") (pinfunction "1_1") (pintype "passive"))
    )
    (net (code "33") (name "VIN") (class "Default")
      (node (ref "C1") (pin "1") (pinfunction "1_1") (pintype "power_in"))
      (node (ref "C2") (pin "1") (pinfunction "1_1") (pintype "power_in"))
      (node (ref "C3") (pin "2") (pinfunction "2_2") (pintype "passive"))
      (node (ref "C4") (pin "1") (pinfunction "1_1") (pintype "power_in"))
      (node (ref "C5") (pin "2") (pinfunction "2_2") (pintype "passive"))
      (node (ref "C6") (pin "2") (pinfunction "2_2") (pintype "passive"))
      (node (ref "C7") (pin "2") (pinfunction "2_2") (pintype "passive"))
      (node (ref "C9") (pin "1") (pinfunction "1_1") (pintype "power_in"))
      (node (ref "D1") (pin "1") (pinfunction "VIN_1") (pintype "passive"))
      (node (ref "DD1") (pin "5") (pinfunction "VIN_5") (pintype "passive"))
      (node (ref "DD2") (pin "5") (pinfunction "VIN_5") (pintype "passive"))
      (node (ref "R2") (pin "2") (pinfunction "2_2") (pintype "passive"))
      (node (ref "R3") (pin "2") (pinfunction "2_2") (pintype "passive"))
      (node (ref "R5") (pin "1") (pinfunction "1_1") (pintype "passive"))
      (node (ref "R8") (pin "2") (pinfunction "2_2") (pintype "passive"))
      (node (ref "R9") (pin "2") (pinfunction "2_2") (pintype "passive"))
      (node (ref "VD1") (pin "2") (pinfunction "2_2") (pintype "passive"))
      (node (ref "VD2") (pin "2") (pinfunction "2_2") (pintype "passive"))
      (node (ref "XS1") (pin "1") (pinfunction "1_1") (pintype "passive"))
      (node (ref "XS23") (pin "1") (pinfunction "1_1") (pintype "passive"))
    )
    (net (code "34") (name "unconnected-(D1-PG-Pad7)") (class "Default")
      (node (ref "D1") (pin "7") (pinfunction "PG_7") (pintype "passive"))
    )
  )
)
